# core.net
KiCad netlist of a schematic drawn in EAGLE
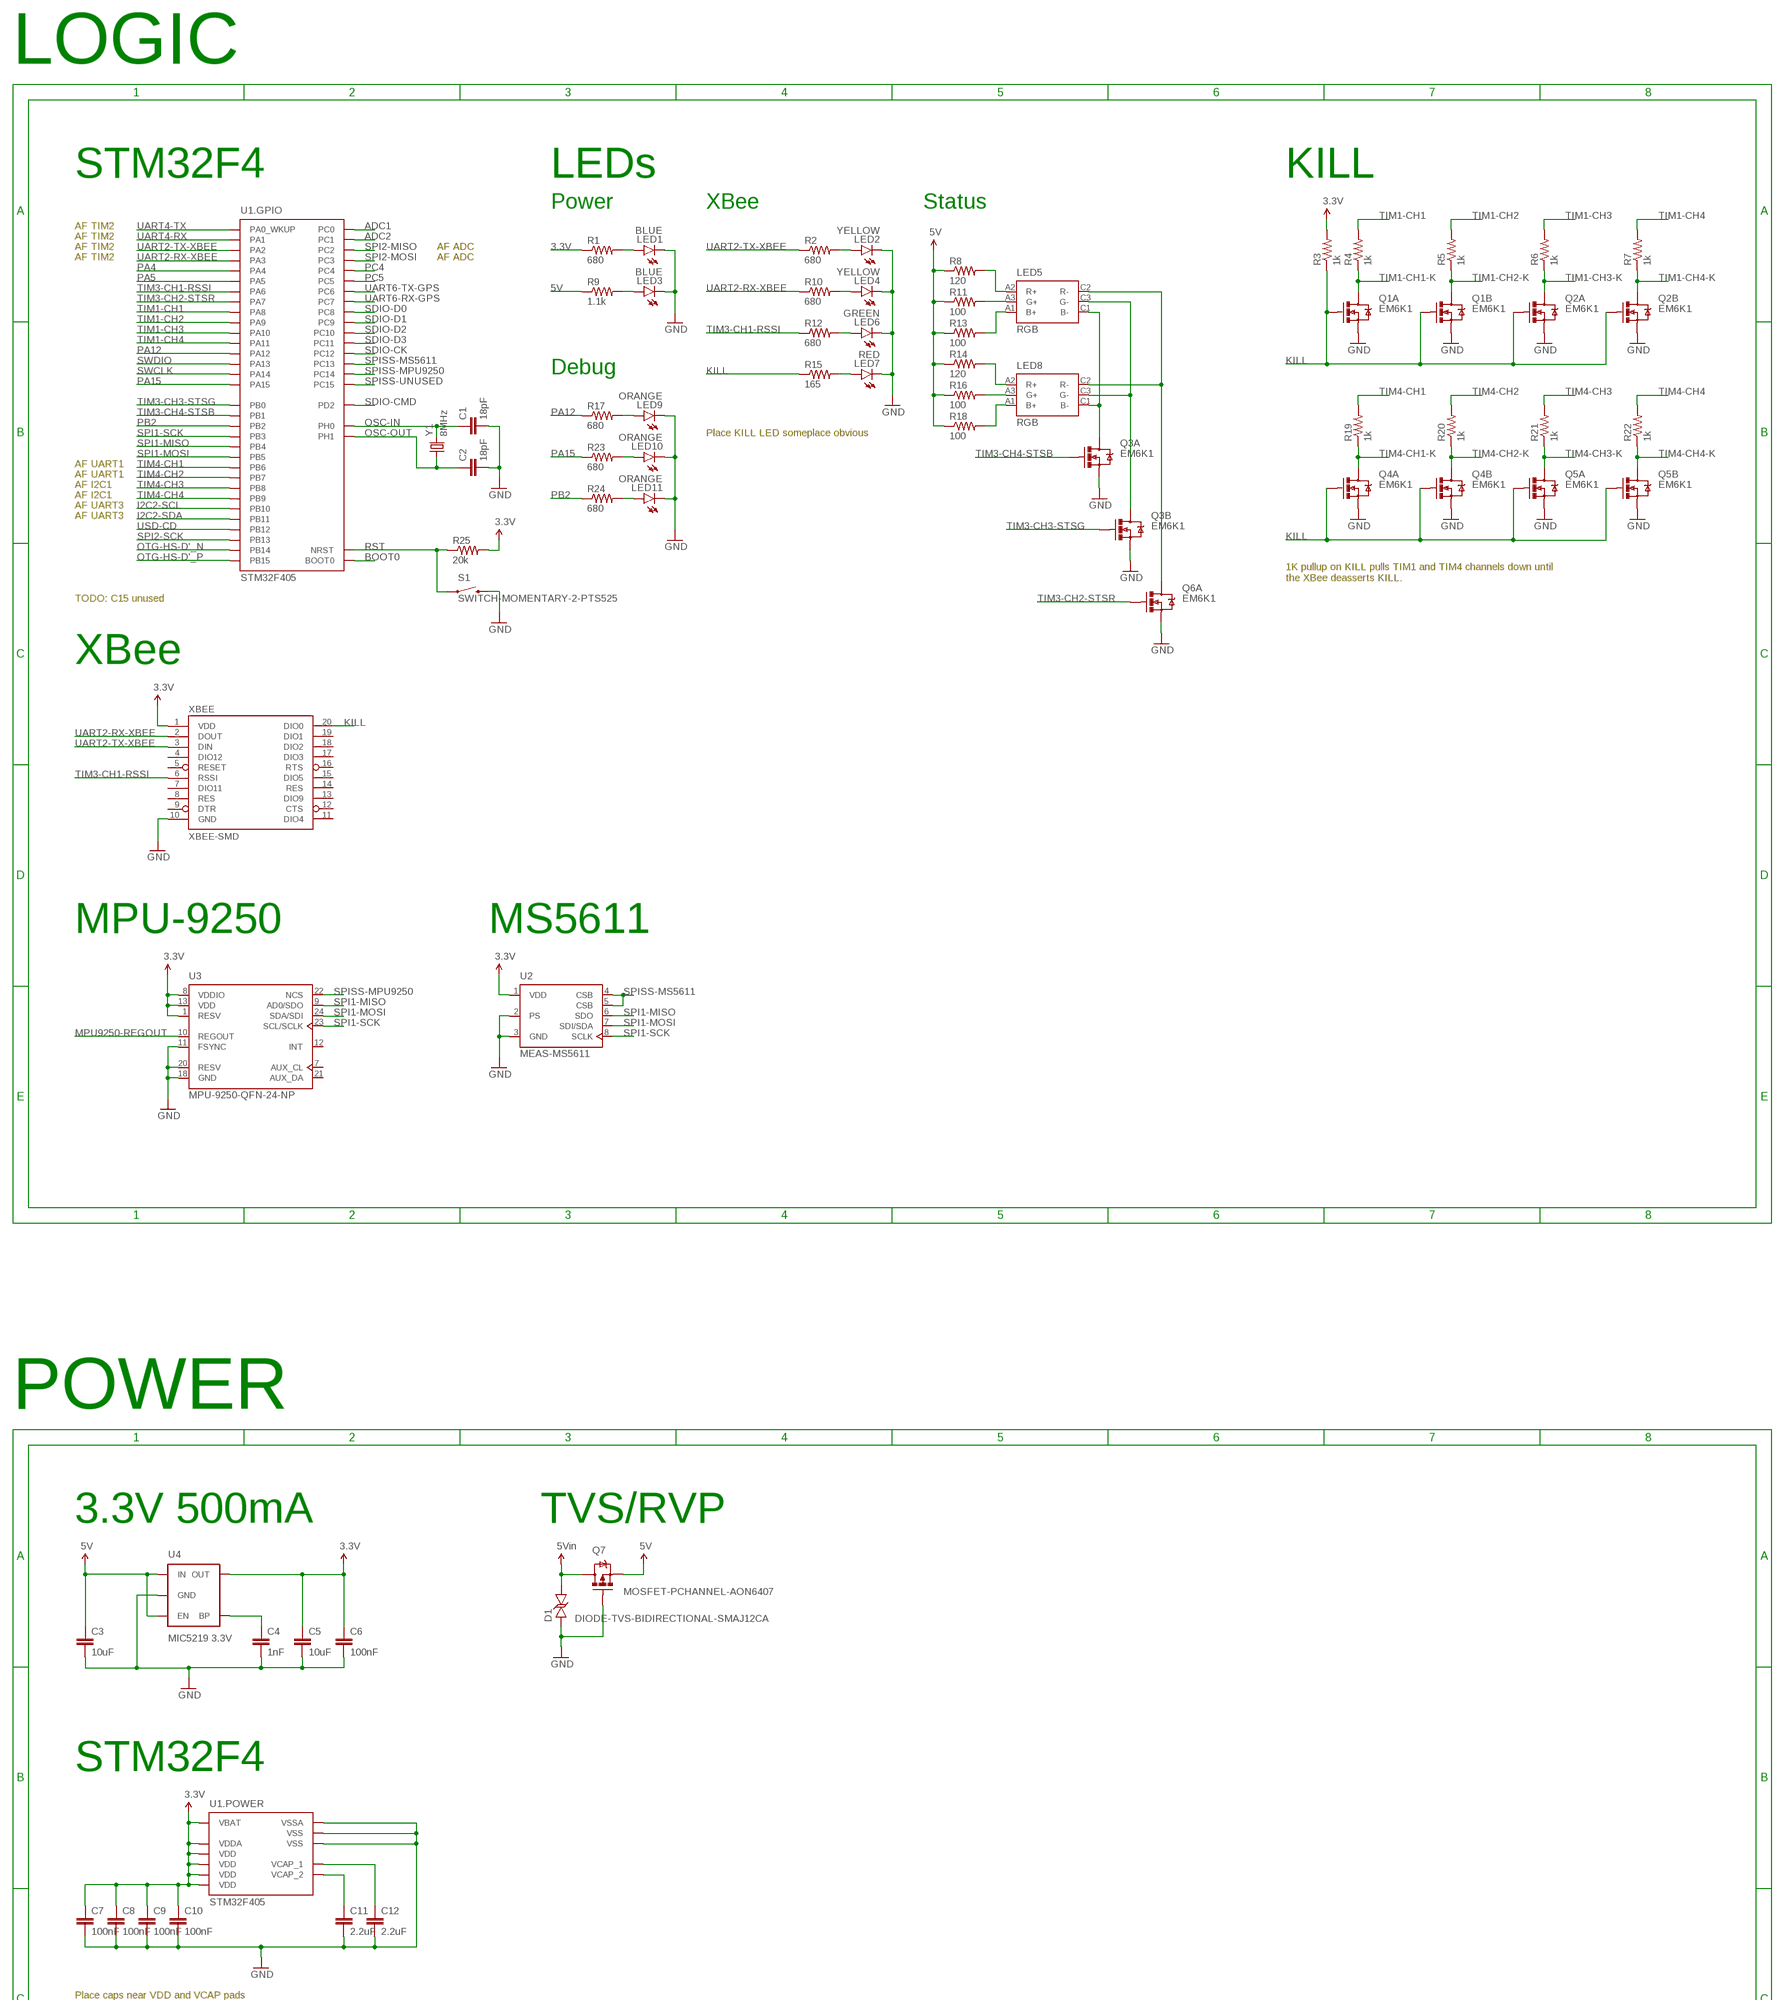
[diagram p0: schematic, sheet 1, part 1 of 2]
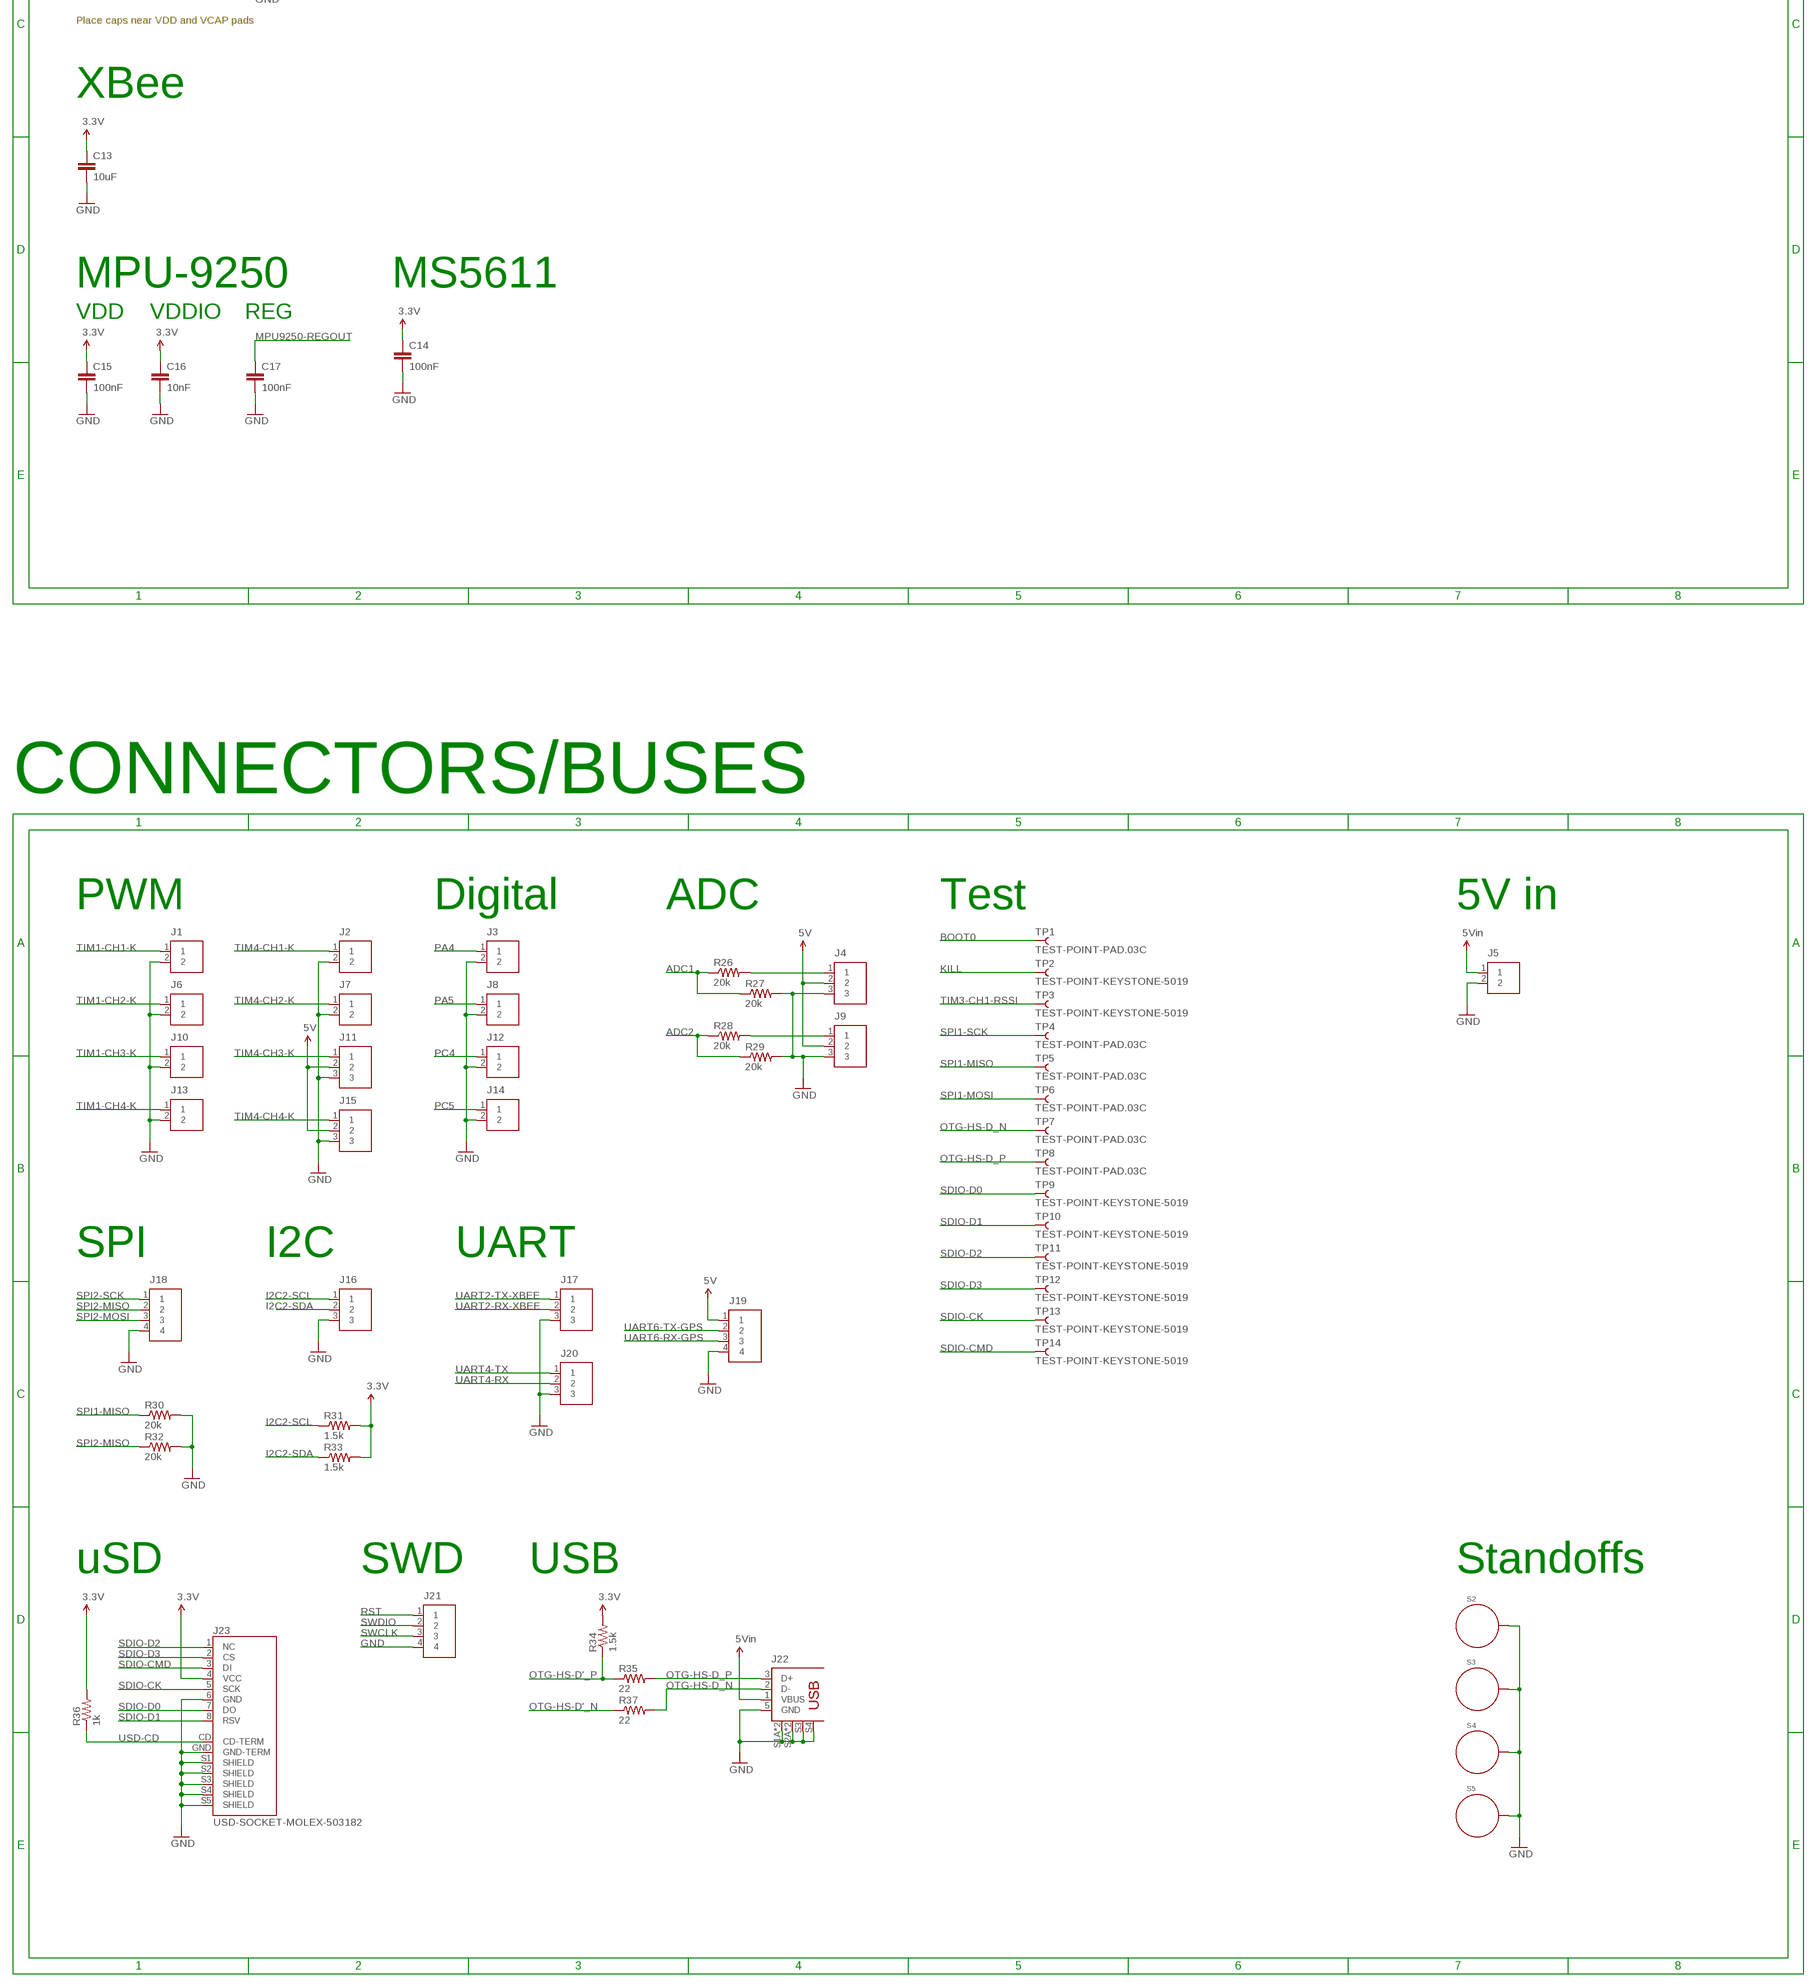
[diagram p1: schematic, sheet 1, part 2 of 2]

(export (version "E")
  (design (tool "Eeschema 10.0.6"))
  (components
    (comp (ref "C1")
      (value "18pF")
      (footprint "eagle-import:0603")
      (libsource (lib "eagle-import") (part "CAP-18PF-50V-5%(0603)"))
    )
    (comp (ref "C2")
      (value "18pF")
      (footprint "eagle-import:0603")
      (libsource (lib "eagle-import") (part "CAP-18PF-50V-5%(0603)"))
    )
    (comp (ref "C3")
      (value "10uF")
      (footprint "eagle-import:0805")
      (libsource (lib "eagle-import") (part "CAP-10UF-10V-10%(0805)"))
    )
    (comp (ref "C4")
      (value "1nF")
      (footprint "eagle-import:0603")
      (libsource (lib "eagle-import") (part "CAP-1NF-50V-10%(0603)"))
    )
    (comp (ref "C5")
      (value "10uF")
      (footprint "eagle-import:0805")
      (libsource (lib "eagle-import") (part "CAP-10UF-10V-10%(0805)"))
    )
    (comp (ref "C6")
      (value "100nF")
      (footprint "eagle-import:0603")
      (libsource (lib "eagle-import") (part "CAP-100NF-16V-10%(0603)"))
    )
    (comp (ref "C7")
      (value "100nF")
      (footprint "eagle-import:0603")
      (libsource (lib "eagle-import") (part "CAP-100NF-16V-10%(0603)"))
    )
    (comp (ref "C8")
      (value "100nF")
      (footprint "eagle-import:0603")
      (libsource (lib "eagle-import") (part "CAP-100NF-16V-10%(0603)"))
    )
    (comp (ref "C9")
      (value "100nF")
      (footprint "eagle-import:0603")
      (libsource (lib "eagle-import") (part "CAP-100NF-16V-10%(0603)"))
    )
    (comp (ref "C10")
      (value "100nF")
      (footprint "eagle-import:0603")
      (libsource (lib "eagle-import") (part "CAP-100NF-16V-10%(0603)"))
    )
    (comp (ref "C11")
      (value "2.2uF")
      (footprint "eagle-import:0603")
      (libsource (lib "eagle-import") (part "CAP-2.2UF-10V-10%(0603)"))
    )
    (comp (ref "C12")
      (value "2.2uF")
      (footprint "eagle-import:0603")
      (libsource (lib "eagle-import") (part "CAP-2.2UF-10V-10%(0603)"))
    )
    (comp (ref "C13")
      (value "10uF")
      (footprint "eagle-import:0805")
      (libsource (lib "eagle-import") (part "CAP-10UF-10V-10%(0805)"))
    )
    (comp (ref "C14")
      (value "100nF")
      (footprint "eagle-import:0603")
      (libsource (lib "eagle-import") (part "CAP-100NF-16V-10%(0603)"))
    )
    (comp (ref "C15")
      (value "100nF")
      (footprint "eagle-import:0603")
      (libsource (lib "eagle-import") (part "CAP-100NF-16V-10%(0603)"))
    )
    (comp (ref "C16")
      (value "10nF")
      (footprint "eagle-import:0603")
      (libsource (lib "eagle-import") (part "CAP-10NF-50V-10%(0603)"))
    )
    (comp (ref "C17")
      (value "100nF")
      (footprint "eagle-import:0603")
      (libsource (lib "eagle-import") (part "CAP-100NF-16V-10%(0603)"))
    )
    (comp (ref "D1")
      (value "DIODE-TVS-BIDIRECTIONAL-SMAJ12CA")
      (footprint "eagle-import:SMAJ")
      (libsource (lib "eagle-import") (part "DIODE-TVS-BIDIRECTIONAL-SMAJ12CA"))
    )
    (comp (ref "J1")
      (value "M02")
      (footprint "eagle-import:MOLEX-2MM-MICROLATCH-2POS-RA")
      (libsource (lib "eagle-import") (part "M02"))
    )
    (comp (ref "J2")
      (value "M02")
      (footprint "eagle-import:MOLEX-2MM-MICROLATCH-2POS-RA")
      (libsource (lib "eagle-import") (part "M02"))
    )
    (comp (ref "J3")
      (value "M02")
      (footprint "eagle-import:MOLEX-2MM-MICROLATCH-2POS-RA")
      (libsource (lib "eagle-import") (part "M02"))
    )
    (comp (ref "J4")
      (value "M03")
      (footprint "eagle-import:MOLEX-2MM-MICROLATCH-3POS-RA")
      (libsource (lib "eagle-import") (part "M03"))
    )
    (comp (ref "J5")
      (value "M02")
      (footprint "eagle-import:MOLEX-2MM-MICROLATCH-2POS-RA")
      (libsource (lib "eagle-import") (part "M02"))
    )
    (comp (ref "J6")
      (value "M02")
      (footprint "eagle-import:MOLEX-2MM-MICROLATCH-2POS-RA")
      (libsource (lib "eagle-import") (part "M02"))
    )
    (comp (ref "J7")
      (value "M02")
      (footprint "eagle-import:MOLEX-2MM-MICROLATCH-2POS-RA")
      (libsource (lib "eagle-import") (part "M02"))
    )
    (comp (ref "J8")
      (value "M02")
      (footprint "eagle-import:MOLEX-2MM-MICROLATCH-2POS-RA")
      (libsource (lib "eagle-import") (part "M02"))
    )
    (comp (ref "J9")
      (value "M03")
      (footprint "eagle-import:MOLEX-2MM-MICROLATCH-3POS-RA")
      (libsource (lib "eagle-import") (part "M03"))
    )
    (comp (ref "J10")
      (value "M02")
      (footprint "eagle-import:MOLEX-2MM-MICROLATCH-2POS-RA")
      (libsource (lib "eagle-import") (part "M02"))
    )
    (comp (ref "J11")
      (value "M03")
      (footprint "eagle-import:MOLEX-2MM-MICROLATCH-3POS-RA")
      (libsource (lib "eagle-import") (part "M03"))
    )
    (comp (ref "J12")
      (value "M02")
      (footprint "eagle-import:MOLEX-2MM-MICROLATCH-2POS-RA")
      (libsource (lib "eagle-import") (part "M02"))
    )
    (comp (ref "J13")
      (value "M02")
      (footprint "eagle-import:MOLEX-2MM-MICROLATCH-2POS-RA")
      (libsource (lib "eagle-import") (part "M02"))
    )
    (comp (ref "J14")
      (value "M02")
      (footprint "eagle-import:MOLEX-2MM-MICROLATCH-2POS-RA")
      (libsource (lib "eagle-import") (part "M02"))
    )
    (comp (ref "J15")
      (value "M03")
      (footprint "eagle-import:MOLEX-2MM-MICROLATCH-3POS-RA")
      (libsource (lib "eagle-import") (part "M03"))
    )
    (comp (ref "J16")
      (value "M03")
      (footprint "eagle-import:MOLEX-2MM-MICROLATCH-3POS-RA")
      (libsource (lib "eagle-import") (part "M03"))
    )
    (comp (ref "J17")
      (value "M03")
      (footprint "eagle-import:MOLEX-2MM-MICROLATCH-3POS-RA")
      (libsource (lib "eagle-import") (part "M03"))
    )
    (comp (ref "J18")
      (value "M04")
      (footprint "eagle-import:MOLEX-2MM-MICROLATCH-4POS-RA")
      (libsource (lib "eagle-import") (part "M04"))
    )
    (comp (ref "J19")
      (value "M04")
      (footprint "eagle-import:MOLEX-2MM-MICROLATCH-4POS-RA")
      (libsource (lib "eagle-import") (part "M04"))
    )
    (comp (ref "J20")
      (value "M03")
      (footprint "eagle-import:MOLEX-2MM-MICROLATCH-3POS-RA")
      (libsource (lib "eagle-import") (part "M03"))
    )
    (comp (ref "J21")
      (value "M04")
      (footprint "eagle-import:MOLEX-2MM-MICROLATCH-4POS-RA")
      (libsource (lib "eagle-import") (part "M04"))
    )
    (comp (ref "J22")
      (value "USB+SHIELD-MICROB-SMD-MOLEX")
      (footprint "eagle-import:USB-MICROB-SMD-MOLEX")
      (libsource (lib "eagle-import") (part "USB+SHIELD-MICROB-SMD-MOLEX"))
    )
    (comp (ref "J23")
      (value "USD-SOCKET-MOLEX-503182")
      (footprint "eagle-import:USD-SOCKET-PP-MOLEX-503182")
      (libsource (lib "eagle-import") (part "USD-SOCKET-MOLEX-503182"))
    )
    (comp (ref "LED1")
      (value "BLUE")
      (footprint "eagle-import:LED-0603")
      (libsource (lib "eagle-import") (part "LED-KINGBRIGHT-HELI-BLUE(0603)"))
    )
    (comp (ref "LED2")
      (value "YELLOW")
      (footprint "eagle-import:LED-0603")
      (libsource (lib "eagle-import") (part "LED-KINGBRIGHT-HELI-YELLOW(0603)"))
    )
    (comp (ref "LED3")
      (value "BLUE")
      (footprint "eagle-import:LED-0603")
      (libsource (lib "eagle-import") (part "LED-KINGBRIGHT-HELI-BLUE(0603)"))
    )
    (comp (ref "LED4")
      (value "YELLOW")
      (footprint "eagle-import:LED-0603")
      (libsource (lib "eagle-import") (part "LED-KINGBRIGHT-HELI-YELLOW(0603)"))
    )
    (comp (ref "LED5")
      (value "RGB")
      (footprint "eagle-import:PLCC-6")
      (libsource (lib "eagle-import") (part "OSRAM-MULTILED-RGB"))
    )
    (comp (ref "LED6")
      (value "GREEN")
      (footprint "eagle-import:LED-0603")
      (libsource (lib "eagle-import") (part "LED-KINGBRIGHT-HELI-GREEN(0603)"))
    )
    (comp (ref "LED7")
      (value "RED")
      (footprint "eagle-import:LED-0603")
      (libsource (lib "eagle-import") (part "LED-KINGBRIGHT-HELI-RED(0603)"))
    )
    (comp (ref "LED8")
      (value "RGB")
      (footprint "eagle-import:PLCC-6")
      (libsource (lib "eagle-import") (part "OSRAM-MULTILED-RGB"))
    )
    (comp (ref "LED9")
      (value "ORANGE")
      (footprint "eagle-import:LED-0603")
      (libsource (lib "eagle-import") (part "LED-KINGBRIGHT-HELI-ORANGE(0603)"))
    )
    (comp (ref "LED10")
      (value "ORANGE")
      (footprint "eagle-import:LED-0603")
      (libsource (lib "eagle-import") (part "LED-KINGBRIGHT-HELI-ORANGE(0603)"))
    )
    (comp (ref "LED11")
      (value "ORANGE")
      (footprint "eagle-import:LED-0603")
      (libsource (lib "eagle-import") (part "LED-KINGBRIGHT-HELI-ORANGE(0603)"))
    )
    (comp (ref "Q1")
      (value "EM6K1")
      (footprint "eagle-import:SOT-666")
      (libsource (lib "eagle-import") (part "MOSFET-NCHANNEL-DUAL-EM6K1"))
    )
    (comp (ref "Q2")
      (value "EM6K1")
      (footprint "eagle-import:SOT-666")
      (libsource (lib "eagle-import") (part "MOSFET-NCHANNEL-DUAL-EM6K1"))
    )
    (comp (ref "Q3")
      (value "EM6K1")
      (footprint "eagle-import:SOT-666")
      (libsource (lib "eagle-import") (part "MOSFET-NCHANNEL-DUAL-EM6K1"))
    )
    (comp (ref "Q4")
      (value "EM6K1")
      (footprint "eagle-import:SOT-666")
      (libsource (lib "eagle-import") (part "MOSFET-NCHANNEL-DUAL-EM6K1"))
    )
    (comp (ref "Q5")
      (value "EM6K1")
      (footprint "eagle-import:SOT-666")
      (libsource (lib "eagle-import") (part "MOSFET-NCHANNEL-DUAL-EM6K1"))
    )
    (comp (ref "Q6")
      (value "EM6K1")
      (footprint "eagle-import:SOT-666")
      (libsource (lib "eagle-import") (part "MOSFET-NCHANNEL-DUAL-EM6K1"))
    )
    (comp (ref "Q7")
      (value "MOSFET-PCHANNEL-AON6407")
      (footprint "eagle-import:DFN5X6")
      (libsource (lib "eagle-import") (part "MOSFET-PCHANNEL-AON6407"))
    )
    (comp (ref "R1")
      (value "680")
      (footprint "eagle-import:0603")
      (libsource (lib "eagle-import") (part "RES-680OHM-0.1W-5%(0603)"))
    )
    (comp (ref "R2")
      (value "680")
      (footprint "eagle-import:0603")
      (libsource (lib "eagle-import") (part "RES-680OHM-0.1W-5%(0603)"))
    )
    (comp (ref "R3")
      (value "1k")
      (footprint "eagle-import:0603")
      (libsource (lib "eagle-import") (part "RES-1KOHM-0.1W-5%(0603)"))
    )
    (comp (ref "R4")
      (value "1k")
      (footprint "eagle-import:0603")
      (libsource (lib "eagle-import") (part "RES-1KOHM-0.1W-5%(0603)"))
    )
    (comp (ref "R5")
      (value "1k")
      (footprint "eagle-import:0603")
      (libsource (lib "eagle-import") (part "RES-1KOHM-0.1W-5%(0603)"))
    )
    (comp (ref "R6")
      (value "1k")
      (footprint "eagle-import:0603")
      (libsource (lib "eagle-import") (part "RES-1KOHM-0.1W-5%(0603)"))
    )
    (comp (ref "R7")
      (value "1k")
      (footprint "eagle-import:0603")
      (libsource (lib "eagle-import") (part "RES-1KOHM-0.1W-5%(0603)"))
    )
    (comp (ref "R8")
      (value "120")
      (footprint "eagle-import:0603")
      (libsource (lib "eagle-import") (part "RES-120OHM-0.1W-5%(0603)"))
    )
    (comp (ref "R9")
      (value "1.1k")
      (footprint "eagle-import:0603")
      (libsource (lib "eagle-import") (part "RES-1.1KOHM-0.1W-5%(0603)"))
    )
    (comp (ref "R10")
      (value "680")
      (footprint "eagle-import:0603")
      (libsource (lib "eagle-import") (part "RES-680OHM-0.1W-5%(0603)"))
    )
    (comp (ref "R11")
      (value "100")
      (footprint "eagle-import:0603")
      (libsource (lib "eagle-import") (part "RES-100OHM-0.1W-5%(0603)"))
    )
    (comp (ref "R12")
      (value "680")
      (footprint "eagle-import:0603")
      (libsource (lib "eagle-import") (part "RES-680OHM-0.1W-5%(0603)"))
    )
    (comp (ref "R13")
      (value "100")
      (footprint "eagle-import:0603")
      (libsource (lib "eagle-import") (part "RES-100OHM-0.1W-5%(0603)"))
    )
    (comp (ref "R14")
      (value "120")
      (footprint "eagle-import:0603")
      (libsource (lib "eagle-import") (part "RES-120OHM-0.1W-5%(0603)"))
    )
    (comp (ref "R15")
      (value "165")
      (footprint "eagle-import:0603")
      (libsource (lib "eagle-import") (part "RES-165OHM-0.1W-1%(0603)"))
    )
    (comp (ref "R16")
      (value "100")
      (footprint "eagle-import:0603")
      (libsource (lib "eagle-import") (part "RES-100OHM-0.1W-5%(0603)"))
    )
    (comp (ref "R17")
      (value "680")
      (footprint "eagle-import:0603")
      (libsource (lib "eagle-import") (part "RES-680OHM-0.1W-5%(0603)"))
    )
    (comp (ref "R18")
      (value "100")
      (footprint "eagle-import:0603")
      (libsource (lib "eagle-import") (part "RES-100OHM-0.1W-5%(0603)"))
    )
    (comp (ref "R19")
      (value "1k")
      (footprint "eagle-import:0603")
      (libsource (lib "eagle-import") (part "RES-1KOHM-0.1W-5%(0603)"))
    )
    (comp (ref "R20")
      (value "1k")
      (footprint "eagle-import:0603")
      (libsource (lib "eagle-import") (part "RES-1KOHM-0.1W-5%(0603)"))
    )
    (comp (ref "R21")
      (value "1k")
      (footprint "eagle-import:0603")
      (libsource (lib "eagle-import") (part "RES-1KOHM-0.1W-5%(0603)"))
    )
    (comp (ref "R22")
      (value "1k")
      (footprint "eagle-import:0603")
      (libsource (lib "eagle-import") (part "RES-1KOHM-0.1W-5%(0603)"))
    )
    (comp (ref "R23")
      (value "680")
      (footprint "eagle-import:0603")
      (libsource (lib "eagle-import") (part "RES-680OHM-0.1W-5%(0603)"))
    )
    (comp (ref "R24")
      (value "680")
      (footprint "eagle-import:0603")
      (libsource (lib "eagle-import") (part "RES-680OHM-0.1W-5%(0603)"))
    )
    (comp (ref "R25")
      (value "20k")
      (footprint "eagle-import:0603")
      (libsource (lib "eagle-import") (part "RES-20KOHM-0.1W-1%(0603)"))
    )
    (comp (ref "R26")
      (value "20k")
      (footprint "eagle-import:0603")
      (libsource (lib "eagle-import") (part "RES-20KOHM-0.1W-0.1%(0603)"))
    )
    (comp (ref "R27")
      (value "20k")
      (footprint "eagle-import:0603")
      (libsource (lib "eagle-import") (part "RES-20KOHM-0.1W-0.1%(0603)"))
    )
    (comp (ref "R28")
      (value "20k")
      (footprint "eagle-import:0603")
      (libsource (lib "eagle-import") (part "RES-20KOHM-0.1W-0.1%(0603)"))
    )
    (comp (ref "R29")
      (value "20k")
      (footprint "eagle-import:0603")
      (libsource (lib "eagle-import") (part "RES-20KOHM-0.1W-0.1%(0603)"))
    )
    (comp (ref "R30")
      (value "20k")
      (footprint "eagle-import:0603")
      (libsource (lib "eagle-import") (part "RES-20KOHM-0.1W-1%(0603)"))
    )
    (comp (ref "R31")
      (value "1.5k")
      (footprint "eagle-import:0603")
      (libsource (lib "eagle-import") (part "RES-1.5KOHM-0.1W-5%(0603)"))
    )
    (comp (ref "R32")
      (value "20k")
      (footprint "eagle-import:0603")
      (libsource (lib "eagle-import") (part "RES-20KOHM-0.1W-1%(0603)"))
    )
    (comp (ref "R33")
      (value "1.5k")
      (footprint "eagle-import:0603")
      (libsource (lib "eagle-import") (part "RES-1.5KOHM-0.1W-5%(0603)"))
    )
    (comp (ref "R34")
      (value "1.5k")
      (footprint "eagle-import:0603")
      (libsource (lib "eagle-import") (part "RES-1.5KOHM-0.1W-5%(0603)"))
    )
    (comp (ref "R35")
      (value "22")
      (footprint "eagle-import:0603")
      (libsource (lib "eagle-import") (part "RES-22OHM-0.1W-5%(0603)"))
    )
    (comp (ref "R36")
      (value "1k")
      (footprint "eagle-import:0603")
      (libsource (lib "eagle-import") (part "RES-1KOHM-0.1W-5%(0603)"))
    )
    (comp (ref "R37")
      (value "22")
      (footprint "eagle-import:0603")
      (libsource (lib "eagle-import") (part "RES-22OHM-0.1W-5%(0603)"))
    )
    (comp (ref "S1")
      (value "SWITCH-MOMENTARY-2-PTS525")
      (footprint "eagle-import:TACTILE-SWITCH-SMD")
      (libsource (lib "eagle-import") (part "SWITCH-MOMENTARY-2-PTS525"))
    )
    (comp (ref "S2")
      (value "STANDOFF_ELECTRICAL-#4")
      (footprint "eagle-import:STANDOFF-ELECTRICAL-#4")
      (libsource (lib "eagle-import") (part "STANDOFF_ELECTRICAL-#4"))
    )
    (comp (ref "S3")
      (value "STANDOFF_ELECTRICAL-#4")
      (footprint "eagle-import:STANDOFF-ELECTRICAL-#4")
      (libsource (lib "eagle-import") (part "STANDOFF_ELECTRICAL-#4"))
    )
    (comp (ref "S4")
      (value "STANDOFF_ELECTRICAL-#4")
      (footprint "eagle-import:STANDOFF-ELECTRICAL-#4")
      (libsource (lib "eagle-import") (part "STANDOFF_ELECTRICAL-#4"))
    )
    (comp (ref "S5")
      (value "STANDOFF_ELECTRICAL-#4")
      (footprint "eagle-import:STANDOFF-ELECTRICAL-#4")
      (libsource (lib "eagle-import") (part "STANDOFF_ELECTRICAL-#4"))
    )
    (comp (ref "TP1")
      (value "TEST-POINT-PAD.03C")
      (footprint "eagle-import:PAD-.03C")
      (libsource (lib "eagle-import") (part "TEST-POINT-PAD.03C"))
    )
    (comp (ref "TP2")
      (value "TEST-POINT-KEYSTONE-5019")
      (footprint "eagle-import:PAD.15X.08")
      (libsource (lib "eagle-import") (part "TEST-POINT-KEYSTONE-5019"))
    )
    (comp (ref "TP3")
      (value "TEST-POINT-KEYSTONE-5019")
      (footprint "eagle-import:PAD.15X.08")
      (libsource (lib "eagle-import") (part "TEST-POINT-KEYSTONE-5019"))
    )
    (comp (ref "TP4")
      (value "TEST-POINT-PAD.03C")
      (footprint "eagle-import:PAD-.03C")
      (libsource (lib "eagle-import") (part "TEST-POINT-PAD.03C"))
    )
    (comp (ref "TP5")
      (value "TEST-POINT-PAD.03C")
      (footprint "eagle-import:PAD-.03C")
      (libsource (lib "eagle-import") (part "TEST-POINT-PAD.03C"))
    )
    (comp (ref "TP6")
      (value "TEST-POINT-PAD.03C")
      (footprint "eagle-import:PAD-.03C")
      (libsource (lib "eagle-import") (part "TEST-POINT-PAD.03C"))
    )
    (comp (ref "TP7")
      (value "TEST-POINT-PAD.03C")
      (footprint "eagle-import:PAD-.03C")
      (libsource (lib "eagle-import") (part "TEST-POINT-PAD.03C"))
    )
    (comp (ref "TP8")
      (value "TEST-POINT-PAD.03C")
      (footprint "eagle-import:PAD-.03C")
      (libsource (lib "eagle-import") (part "TEST-POINT-PAD.03C"))
    )
    (comp (ref "TP9")
      (value "TEST-POINT-KEYSTONE-5019")
      (footprint "eagle-import:PAD.15X.08")
      (libsource (lib "eagle-import") (part "TEST-POINT-KEYSTONE-5019"))
    )
    (comp (ref "TP10")
      (value "TEST-POINT-KEYSTONE-5019")
      (footprint "eagle-import:PAD.15X.08")
      (libsource (lib "eagle-import") (part "TEST-POINT-KEYSTONE-5019"))
    )
    (comp (ref "TP11")
      (value "TEST-POINT-KEYSTONE-5019")
      (footprint "eagle-import:PAD.15X.08")
      (libsource (lib "eagle-import") (part "TEST-POINT-KEYSTONE-5019"))
    )
    (comp (ref "TP12")
      (value "TEST-POINT-KEYSTONE-5019")
      (footprint "eagle-import:PAD.15X.08")
      (libsource (lib "eagle-import") (part "TEST-POINT-KEYSTONE-5019"))
    )
    (comp (ref "TP13")
      (value "TEST-POINT-KEYSTONE-5019")
      (footprint "eagle-import:PAD.15X.08")
      (libsource (lib "eagle-import") (part "TEST-POINT-KEYSTONE-5019"))
    )
    (comp (ref "TP14")
      (value "TEST-POINT-KEYSTONE-5019")
      (footprint "eagle-import:PAD.15X.08")
      (libsource (lib "eagle-import") (part "TEST-POINT-KEYSTONE-5019"))
    )
    (comp (ref "U1")
      (value "STM32F405")
      (footprint "eagle-import:LQFP-64-STM32F405")
      (libsource (lib "eagle-import") (part "STM32F405"))
    )
    (comp (ref "U2")
      (value "MEAS-MS5611")
      (footprint "eagle-import:MEAS-MS5611")
      (libsource (lib "eagle-import") (part "MEAS-MS5611"))
    )
    (comp (ref "U3")
      (value "MPU-9250-QFN-24-NP")
      (footprint "eagle-import:QFN-24-NP")
      (libsource (lib "eagle-import") (part "MPU-9250-QFN-24-NP"))
    )
    (comp (ref "U4")
      (value "MIC5219 3.3V")
      (footprint "eagle-import:SOT23-5")
      (libsource (lib "eagle-import") (part "V-REG-MIC5219-3.3V"))
    )
    (comp (ref "XBEE")
      (value "XBEE-SMD")
      (footprint "eagle-import:XBEE-SMD")
      (libsource (lib "eagle-import") (part "XBEE-SMD"))
    )
    (comp (ref "Y1")
      (value "8MHz")
      (footprint "eagle-import:CX532")
      (libsource (lib "eagle-import") (part "CRYSTAL-8MHZ-CX532"))
    )
  )
  (nets
    (net (code "1") (name "/ADC1") (class "Default")
      (node (ref "R26") (pin "1") (pinfunction "1_1") (pintype "passive"))
      (node (ref "R27") (pin "1") (pinfunction "1_1") (pintype "passive"))
      (node (ref "U1") (pin "8") (pinfunction "PC0_8") (pintype "bidirectional"))
    )
    (net (code "2") (name "/ADC2") (class "Default")
      (node (ref "R28") (pin "1") (pinfunction "1_1") (pintype "passive"))
      (node (ref "R29") (pin "1") (pinfunction "1_1") (pintype "passive"))
      (node (ref "U1") (pin "9") (pinfunction "PC1_9") (pintype "bidirectional"))
    )
    (net (code "3") (name "/BOOT0") (class "Default")
      (node (ref "TP1") (pin "1") (pinfunction "1_1") (pintype "bidirectional"))
      (node (ref "U1") (pin "60") (pinfunction "BOOT0_60") (pintype "bidirectional"))
    )
    (net (code "4") (name "/I2C2-SCL") (class "Default")
      (node (ref "J16") (pin "1") (pinfunction "1_1") (pintype "bidirectional"))
      (node (ref "R31") (pin "1") (pinfunction "1_1") (pintype "passive"))
      (node (ref "U1") (pin "29") (pinfunction "PB10_29") (pintype "bidirectional"))
    )
    (net (code "5") (name "/I2C2-SDA") (class "Default")
      (node (ref "J16") (pin "2") (pinfunction "2_2") (pintype "bidirectional"))
      (node (ref "R33") (pin "1") (pinfunction "1_1") (pintype "passive"))
      (node (ref "U1") (pin "30") (pinfunction "PB11_30") (pintype "bidirectional"))
    )
    (net (code "6") (name "/KILL") (class "Default")
      (node (ref "Q1") (pin "2") (pinfunction "G_2") (pintype "passive"))
      (node (ref "Q1") (pin "5") (pinfunction "G_5") (pintype "passive"))
      (node (ref "Q2") (pin "2") (pinfunction "G_2") (pintype "passive"))
      (node (ref "Q2") (pin "5") (pinfunction "G_5") (pintype "passive"))
      (node (ref "Q4") (pin "2") (pinfunction "G_2") (pintype "passive"))
      (node (ref "Q4") (pin "5") (pinfunction "G_5") (pintype "passive"))
      (node (ref "Q5") (pin "2") (pinfunction "G_2") (pintype "passive"))
      (node (ref "Q5") (pin "5") (pinfunction "G_5") (pintype "passive"))
      (node (ref "R15") (pin "1") (pinfunction "1_1") (pintype "passive"))
      (node (ref "R3") (pin "1") (pinfunction "1_1") (pintype "passive"))
      (node (ref "TP2") (pin "1") (pinfunction "1_1") (pintype "bidirectional"))
      (node (ref "XBEE") (pin "20") (pinfunction "DIO0_20") (pintype "bidirectional"))
    )
    (net (code "7") (name "/MPU9250-REGOUT") (class "Default")
      (node (ref "C17") (pin "2") (pinfunction "2_2") (pintype "passive"))
      (node (ref "U3") (pin "10") (pinfunction "REGOUT_10") (pintype "bidirectional"))
    )
    (net (code "8") (name "/OSC-IN") (class "Default")
      (node (ref "C1") (pin "2") (pinfunction "2_2") (pintype "passive"))
      (node (ref "U1") (pin "5") (pinfunction "PH0_5") (pintype "bidirectional"))
      (node (ref "Y1") (pin "2") (pinfunction "2_2") (pintype "passive"))
    )
    (net (code "9") (name "/OSC-OUT") (class "Default")
      (node (ref "C2") (pin "2") (pinfunction "2_2") (pintype "passive"))
      (node (ref "U1") (pin "6") (pinfunction "PH1_6") (pintype "bidirectional"))
      (node (ref "Y1") (pin "1") (pinfunction "1_1") (pintype "passive"))
    )
    (net (code "10") (name "/OTG-HS-D'_N") (class "Default")
      (node (ref "R37") (pin "1") (pinfunction "1_1") (pintype "passive"))
      (node (ref "U1") (pin "35") (pinfunction "PB14_35") (pintype "bidirectional"))
    )
    (net (code "11") (name "/OTG-HS-D'_P") (class "Default")
      (node (ref "R34") (pin "1") (pinfunction "1_1") (pintype "passive"))
      (node (ref "R35") (pin "1") (pinfunction "1_1") (pintype "passive"))
      (node (ref "U1") (pin "36") (pinfunction "PB15_36") (pintype "bidirectional"))
    )
    (net (code "12") (name "/OTG-HS-D_N") (class "Default")
      (node (ref "J22") (pin "2") (pinfunction "D-_2") (pintype "bidirectional"))
      (node (ref "R37") (pin "2") (pinfunction "2_2") (pintype "passive"))
      (node (ref "TP7") (pin "1") (pinfunction "1_1") (pintype "bidirectional"))
    )
    (net (code "13") (name "/OTG-HS-D_P") (class "Default")
      (node (ref "J22") (pin "3") (pinfunction "D+_3") (pintype "bidirectional"))
      (node (ref "R35") (pin "2") (pinfunction "2_2") (pintype "passive"))
      (node (ref "TP8") (pin "1") (pinfunction "1_1") (pintype "bidirectional"))
    )
    (net (code "14") (name "/PA4") (class "Default")
      (node (ref "J3") (pin "1") (pinfunction "1_1") (pintype "bidirectional"))
      (node (ref "U1") (pin "20") (pinfunction "PA4_20") (pintype "bidirectional"))
    )
    (net (code "15") (name "/PA5") (class "Default")
      (node (ref "J8") (pin "1") (pinfunction "1_1") (pintype "bidirectional"))
      (node (ref "U1") (pin "21") (pinfunction "PA5_21") (pintype "bidirectional"))
    )
    (net (code "16") (name "/PA12") (class "Default")
      (node (ref "R17") (pin "1") (pinfunction "1_1") (pintype "passive"))
      (node (ref "U1") (pin "45") (pinfunction "PA12_45") (pintype "bidirectional"))
    )
    (net (code "17") (name "/PA15") (class "Default")
      (node (ref "R23") (pin "1") (pinfunction "1_1") (pintype "passive"))
      (node (ref "U1") (pin "50") (pinfunction "PA15_50") (pintype "bidirectional"))
    )
    (net (code "18") (name "/PB2") (class "Default")
      (node (ref "R24") (pin "1") (pinfunction "1_1") (pintype "passive"))
      (node (ref "U1") (pin "28") (pinfunction "PB2_28") (pintype "bidirectional"))
    )
    (net (code "19") (name "/PC4") (class "Default")
      (node (ref "J12") (pin "1") (pinfunction "1_1") (pintype "bidirectional"))
      (node (ref "U1") (pin "24") (pinfunction "PC4_24") (pintype "bidirectional"))
    )
    (net (code "20") (name "/PC5") (class "Default")
      (node (ref "J14") (pin "1") (pinfunction "1_1") (pintype "bidirectional"))
      (node (ref "U1") (pin "25") (pinfunction "PC5_25") (pintype "bidirectional"))
    )
    (net (code "21") (name "/RST") (class "Default")
      (node (ref "J21") (pin "1") (pinfunction "1_1") (pintype "bidirectional"))
      (node (ref "R25") (pin "1") (pinfunction "1_1") (pintype "passive"))
      (node (ref "S1") (pin "1") (pinfunction "1_1") (pintype "passive"))
      (node (ref "S1") (pin "2") (pinfunction "1_2") (pintype "passive"))
      (node (ref "U1") (pin "7") (pinfunction "NRST_7") (pintype "bidirectional"))
    )
    (net (code "22") (name "/SDIO-CK") (class "Default")
      (node (ref "J23") (pin "5") (pinfunction "SCK_5") (pintype "bidirectional"))
      (node (ref "TP13") (pin "1") (pinfunction "1_1") (pintype "bidirectional"))
      (node (ref "U1") (pin "53") (pinfunction "PC12_53") (pintype "bidirectional"))
    )
    (net (code "23") (name "/SDIO-CMD") (class "Default")
      (node (ref "J23") (pin "3") (pinfunction "DI_3") (pintype "bidirectional"))
      (node (ref "TP14") (pin "1") (pinfunction "1_1") (pintype "bidirectional"))
      (node (ref "U1") (pin "54") (pinfunction "PD2_54") (pintype "bidirectional"))
    )
    (net (code "24") (name "/SDIO-D0") (class "Default")
      (node (ref "J23") (pin "7") (pinfunction "DO_7") (pintype "bidirectional"))
      (node (ref "TP9") (pin "1") (pinfunction "1_1") (pintype "bidirectional"))
      (node (ref "U1") (pin "39") (pinfunction "PC8_39") (pintype "bidirectional"))
    )
    (net (code "25") (name "/SDIO-D1") (class "Default")
      (node (ref "J23") (pin "8") (pinfunction "RSV_8") (pintype "bidirectional"))
      (node (ref "TP10") (pin "1") (pinfunction "1_1") (pintype "bidirectional"))
      (node (ref "U1") (pin "40") (pinfunction "PC9_40") (pintype "bidirectional"))
    )
    (net (code "26") (name "/SDIO-D2") (class "Default")
      (node (ref "J23") (pin "1") (pinfunction "NC_1") (pintype "bidirectional"))
      (node (ref "TP11") (pin "1") (pinfunction "1_1") (pintype "bidirectional"))
      (node (ref "U1") (pin "51") (pinfunction "PC10_51") (pintype "bidirectional"))
    )
    (net (code "27") (name "/SDIO-D3") (class "Default")
      (node (ref "J23") (pin "2") (pinfunction "CS_2") (pintype "bidirectional"))
      (node (ref "TP12") (pin "1") (pinfunction "1_1") (pintype "bidirectional"))
      (node (ref "U1") (pin "52") (pinfunction "PC11_52") (pintype "bidirectional"))
    )
    (net (code "28") (name "/SPI1-MISO") (class "Default")
      (node (ref "R30") (pin "1") (pinfunction "1_1") (pintype "passive"))
      (node (ref "TP5") (pin "1") (pinfunction "1_1") (pintype "bidirectional"))
      (node (ref "U1") (pin "56") (pinfunction "PB4_56") (pintype "bidirectional"))
      (node (ref "U2") (pin "6") (pinfunction "SDO_6") (pintype "output"))
      (node (ref "U3") (pin "9") (pinfunction "AD0/SDO_9") (pintype "bidirectional"))
    )
    (net (code "29") (name "/SPI1-MOSI") (class "Default")
      (node (ref "TP6") (pin "1") (pinfunction "1_1") (pintype "bidirectional"))
      (node (ref "U1") (pin "57") (pinfunction "PB5_57") (pintype "bidirectional"))
      (node (ref "U2") (pin "7") (pinfunction "SDI/SDA_7") (pintype "bidirectional"))
      (node (ref "U3") (pin "24") (pinfunction "SDA/SDI_24") (pintype "bidirectional"))
    )
    (net (code "30") (name "/SPI1-SCK") (class "Default")
      (node (ref "TP4") (pin "1") (pinfunction "1_1") (pintype "bidirectional"))
      (node (ref "U1") (pin "55") (pinfunction "PB3_55") (pintype "bidirectional"))
      (node (ref "U2") (pin "8") (pinfunction "SCLK_8") (pintype "input"))
      (node (ref "U3") (pin "23") (pinfunction "SCL/SCLK_23") (pintype "bidirectional"))
    )
    (net (code "31") (name "/SPI2-MISO") (class "Default")
      (node (ref "J18") (pin "2") (pinfunction "2_2") (pintype "bidirectional"))
      (node (ref "R32") (pin "1") (pinfunction "1_1") (pintype "passive"))
      (node (ref "U1") (pin "10") (pinfunction "PC2_10") (pintype "bidirectional"))
    )
    (net (code "32") (name "/SPI2-MOSI") (class "Default")
      (node (ref "J18") (pin "3") (pinfunction "3_3") (pintype "bidirectional"))
      (node (ref "U1") (pin "11") (pinfunction "PC3_11") (pintype "bidirectional"))
    )
    (net (code "33") (name "/SPI2-SCK") (class "Default")
      (node (ref "J18") (pin "1") (pinfunction "1_1") (pintype "bidirectional"))
      (node (ref "U1") (pin "34") (pinfunction "PB13_34") (pintype "bidirectional"))
    )
    (net (code "34") (name "/SPISS-MPU9250") (class "Default")
      (node (ref "U1") (pin "3") (pinfunction "PC14_3") (pintype "bidirectional"))
      (node (ref "U3") (pin "22") (pinfunction "NCS_22") (pintype "bidirectional"))
    )
    (net (code "35") (name "/SPISS-MS5611") (class "Default")
      (node (ref "U1") (pin "2") (pinfunction "PC13_2") (pintype "bidirectional"))
      (node (ref "U2") (pin "4") (pinfunction "CSB_4") (pintype "input"))
      (node (ref "U2") (pin "5") (pinfunction "CSB_5") (pintype "input"))
    )
    (net (code "36") (name "/SPISS-UNUSED") (class "Default")
      (node (ref "U1") (pin "4") (pinfunction "PC15_4") (pintype "bidirectional"))
    )
    (net (code "37") (name "/SWCLK") (class "Default")
      (node (ref "J21") (pin "3") (pinfunction "3_3") (pintype "bidirectional"))
      (node (ref "U1") (pin "49") (pinfunction "PA14_49") (pintype "bidirectional"))
    )
    (net (code "38") (name "/SWDIO") (class "Default")
      (node (ref "J21") (pin "2") (pinfunction "2_2") (pintype "bidirectional"))
      (node (ref "U1") (pin "46") (pinfunction "PA13_46") (pintype "bidirectional"))
    )
    (net (code "39") (name "/TIM1-CH1") (class "Default")
      (node (ref "R4") (pin "2") (pinfunction "2_2") (pintype "passive"))
      (node (ref "U1") (pin "41") (pinfunction "PA8_41") (pintype "bidirectional"))
    )
    (net (code "40") (name "/TIM1-CH1-K") (class "Default")
      (node (ref "J1") (pin "1") (pinfunction "1_1") (pintype "bidirectional"))
      (node (ref "Q1") (pin "6") (pinfunction "D_6") (pintype "passive"))
      (node (ref "R4") (pin "1") (pinfunction "1_1") (pintype "passive"))
    )
    (net (code "41") (name "/TIM1-CH2") (class "Default")
      (node (ref "R5") (pin "2") (pinfunction "2_2") (pintype "passive"))
      (node (ref "U1") (pin "42") (pinfunction "PA9_42") (pintype "bidirectional"))
    )
    (net (code "42") (name "/TIM1-CH2-K") (class "Default")
      (node (ref "J6") (pin "1") (pinfunction "1_1") (pintype "bidirectional"))
      (node (ref "Q1") (pin "3") (pinfunction "D_3") (pintype "passive"))
      (node (ref "R5") (pin "1") (pinfunction "1_1") (pintype "passive"))
    )
    (net (code "43") (name "/TIM1-CH3") (class "Default")
      (node (ref "R6") (pin "2") (pinfunction "2_2") (pintype "passive"))
      (node (ref "U1") (pin "43") (pinfunction "PA10_43") (pintype "bidirectional"))
    )
    (net (code "44") (name "/TIM1-CH3-K") (class "Default")
      (node (ref "J10") (pin "1") (pinfunction "1_1") (pintype "bidirectional"))
      (node (ref "Q2") (pin "6") (pinfunction "D_6") (pintype "passive"))
      (node (ref "R6") (pin "1") (pinfunction "1_1") (pintype "passive"))
    )
    (net (code "45") (name "/TIM1-CH4") (class "Default")
      (node (ref "R7") (pin "2") (pinfunction "2_2") (pintype "passive"))
      (node (ref "U1") (pin "44") (pinfunction "PA11_44") (pintype "bidirectional"))
    )
    (net (code "46") (name "/TIM1-CH4-K") (class "Default")
      (node (ref "J13") (pin "1") (pinfunction "1_1") (pintype "bidirectional"))
      (node (ref "Q2") (pin "3") (pinfunction "D_3") (pintype "passive"))
      (node (ref "R7") (pin "1") (pinfunction "1_1") (pintype "passive"))
    )
    (net (code "47") (name "/TIM3-CH1-RSSI") (class "Default")
      (node (ref "R12") (pin "1") (pinfunction "1_1") (pintype "passive"))
      (node (ref "TP3") (pin "1") (pinfunction "1_1") (pintype "bidirectional"))
      (node (ref "U1") (pin "22") (pinfunction "PA6_22") (pintype "bidirectional"))
      (node (ref "XBEE") (pin "6") (pinfunction "RSSI_6") (pintype "bidirectional"))
    )
    (net (code "48") (name "/TIM3-CH2-STSR") (class "Default")
      (node (ref "Q6") (pin "2") (pinfunction "G_2") (pintype "passive"))
      (node (ref "U1") (pin "23") (pinfunction "PA7_23") (pintype "bidirectional"))
    )
    (net (code "49") (name "/TIM3-CH3-STSG") (class "Default")
      (node (ref "Q3") (pin "5") (pinfunction "G_5") (pintype "passive"))
      (node (ref "U1") (pin "26") (pinfunction "PB0_26") (pintype "bidirectional"))
    )
    (net (code "50") (name "/TIM3-CH4-STSB") (class "Default")
      (node (ref "Q3") (pin "2") (pinfunction "G_2") (pintype "passive"))
      (node (ref "U1") (pin "27") (pinfunction "PB1_27") (pintype "bidirectional"))
    )
    (net (code "51") (name "/TIM4-CH1") (class "Default")
      (node (ref "R19") (pin "2") (pinfunction "2_2") (pintype "passive"))
      (node (ref "U1") (pin "58") (pinfunction "PB6_58") (pintype "bidirectional"))
    )
    (net (code "52") (name "/TIM4-CH1-K") (class "Default")
      (node (ref "J2") (pin "1") (pinfunction "1_1") (pintype "bidirectional"))
      (node (ref "Q4") (pin "6") (pinfunction "D_6") (pintype "passive"))
      (node (ref "R19") (pin "1") (pinfunction "1_1") (pintype "passive"))
    )
    (net (code "53") (name "/TIM4-CH2") (class "Default")
      (node (ref "R20") (pin "2") (pinfunction "2_2") (pintype "passive"))
      (node (ref "U1") (pin "59") (pinfunction "PB7_59") (pintype "bidirectional"))
    )
    (net (code "54") (name "/TIM4-CH2-K") (class "Default")
      (node (ref "J7") (pin "1") (pinfunction "1_1") (pintype "bidirectional"))
      (node (ref "Q4") (pin "3") (pinfunction "D_3") (pintype "passive"))
      (node (ref "R20") (pin "1") (pinfunction "1_1") (pintype "passive"))
    )
    (net (code "55") (name "/TIM4-CH3") (class "Default")
      (node (ref "R21") (pin "2") (pinfunction "2_2") (pintype "passive"))
      (node (ref "U1") (pin "61") (pinfunction "PB8_61") (pintype "bidirectional"))
    )
    (net (code "56") (name "/TIM4-CH3-K") (class "Default")
      (node (ref "J11") (pin "1") (pinfunction "1_1") (pintype "bidirectional"))
      (node (ref "Q5") (pin "6") (pinfunction "D_6") (pintype "passive"))
      (node (ref "R21") (pin "1") (pinfunction "1_1") (pintype "passive"))
    )
    (net (code "57") (name "/TIM4-CH4") (class "Default")
      (node (ref "R22") (pin "2") (pinfunction "2_2") (pintype "passive"))
      (node (ref "U1") (pin "62") (pinfunction "PB9_62") (pintype "bidirectional"))
    )
    (net (code "58") (name "/TIM4-CH4-K") (class "Default")
      (node (ref "J15") (pin "1") (pinfunction "1_1") (pintype "bidirectional"))
      (node (ref "Q5") (pin "3") (pinfunction "D_3") (pintype "passive"))
      (node (ref "R22") (pin "1") (pinfunction "1_1") (pintype "passive"))
    )
    (net (code "59") (name "/UART2-RX-XBEE") (class "Default")
      (node (ref "J17") (pin "2") (pinfunction "2_2") (pintype "bidirectional"))
      (node (ref "R10") (pin "1") (pinfunction "1_1") (pintype "passive"))
      (node (ref "U1") (pin "17") (pinfunction "PA3_17") (pintype "bidirectional"))
      (node (ref "XBEE") (pin "2") (pinfunction "DOUT_2") (pintype "output"))
    )
    (net (code "60") (name "/UART2-TX-XBEE") (class "Default")
      (node (ref "J17") (pin "1") (pinfunction "1_1") (pintype "bidirectional"))
      (node (ref "R2") (pin "1") (pinfunction "1_1") (pintype "passive"))
      (node (ref "U1") (pin "16") (pinfunction "PA2_16") (pintype "bidirectional"))
      (node (ref "XBEE") (pin "3") (pinfunction "DIN_3") (pintype "input"))
    )
    (net (code "61") (name "/UART4-RX") (class "Default")
      (node (ref "J20") (pin "2") (pinfunction "2_2") (pintype "bidirectional"))
      (node (ref "U1") (pin "15") (pinfunction "PA1_15") (pintype "bidirectional"))
    )
    (net (code "62") (name "/UART4-TX") (class "Default")
      (node (ref "J20") (pin "1") (pinfunction "1_1") (pintype "bidirectional"))
      (node (ref "U1") (pin "14") (pinfunction "PA0_WKUP_14") (pintype "bidirectional"))
    )
    (net (code "63") (name "/UART6-RX-GPS") (class "Default")
      (node (ref "J19") (pin "3") (pinfunction "3_3") (pintype "bidirectional"))
      (node (ref "U1") (pin "38") (pinfunction "PC7_38") (pintype "bidirectional"))
    )
    (net (code "64") (name "/UART6-TX-GPS") (class "Default")
      (node (ref "J19") (pin "2") (pinfunction "2_2") (pintype "bidirectional"))
      (node (ref "U1") (pin "37") (pinfunction "PC6_37") (pintype "bidirectional"))
    )
    (net (code "65") (name "/USD-CD") (class "Default")
      (node (ref "J23") (pin "CD") (pinfunction "CD-TERM_CD") (pintype "bidirectional"))
      (node (ref "R36") (pin "1") (pinfunction "1_1") (pintype "passive"))
      (node (ref "U1") (pin "33") (pinfunction "PB12_33") (pintype "bidirectional"))
    )
    (net (code "66") (name "3.3V") (class "Default")
      (node (ref "C10") (pin "2") (pinfunction "2_2") (pintype "passive"))
      (node (ref "C13") (pin "2") (pinfunction "2_2") (pintype "passive"))
      (node (ref "C14") (pin "2") (pinfunction "2_2") (pintype "passive"))
      (node (ref "C15") (pin "2") (pinfunction "2_2") (pintype "passive"))
      (node (ref "C16") (pin "2") (pinfunction "2_2") (pintype "passive"))
      (node (ref "C5") (pin "2") (pinfunction "2_2") (pintype "passive"))
      (node (ref "C6") (pin "2") (pinfunction "2_2") (pintype "passive"))
      (node (ref "C7") (pin "2") (pinfunction "2_2") (pintype "passive"))
      (node (ref "C8") (pin "2") (pinfunction "2_2") (pintype "passive"))
      (node (ref "C9") (pin "2") (pinfunction "2_2") (pintype "passive"))
      (node (ref "J23") (pin "4") (pinfunction "VCC_4") (pintype "bidirectional"))
      (node (ref "R1") (pin "1") (pinfunction "1_1") (pintype "passive"))
      (node (ref "R25") (pin "2") (pinfunction "2_2") (pintype "passive"))
      (node (ref "R3") (pin "2") (pinfunction "2_2") (pintype "passive"))
      (node (ref "R31") (pin "2") (pinfunction "2_2") (pintype "passive"))
      (node (ref "R33") (pin "2") (pinfunction "2_2") (pintype "passive"))
      (node (ref "R34") (pin "2") (pinfunction "2_2") (pintype "passive"))
      (node (ref "R36") (pin "2") (pinfunction "2_2") (pintype "passive"))
      (node (ref "U1") (pin "1") (pinfunction "VBAT_1") (pintype "power_in"))
      (node (ref "U1") (pin "13") (pinfunction "VDDA_13") (pintype "power_in"))
      (node (ref "U1") (pin "19") (pinfunction "VDD_19") (pintype "power_in"))
      (node (ref "U1") (pin "32") (pinfunction "VDD_32") (pintype "power_in"))
      (node (ref "U1") (pin "48") (pinfunction "VDD_48") (pintype "power_in"))
      (node (ref "U1") (pin "64") (pinfunction "VDD_64") (pintype "power_in"))
      (node (ref "U2") (pin "1") (pinfunction "VDD_1") (pintype "power_in"))
      (node (ref "U3") (pin "1") (pinfunction "RESV_1") (pintype "bidirectional"))
      (node (ref "U3") (pin "13") (pinfunction "VDD_13") (pintype "bidirectional"))
      (node (ref "U3") (pin "8") (pinfunction "VDDIO_8") (pintype "bidirectional"))
      (node (ref "U4") (pin "5") (pinfunction "OUT_5") (pintype "passive"))
      (node (ref "XBEE") (pin "1") (pinfunction "VDD_1") (pintype "power_in"))
    )
    (net (code "67") (name "5V") (class "Default")
      (node (ref "C3") (pin "2") (pinfunction "2_2") (pintype "passive"))
      (node (ref "J11") (pin "2") (pinfunction "2_2") (pintype "bidirectional"))
      (node (ref "J15") (pin "2") (pinfunction "2_2") (pintype "bidirectional"))
      (node (ref "J19") (pin "1") (pinfunction "1_1") (pintype "bidirectional"))
      (node (ref "J4") (pin "2") (pinfunction "2_2") (pintype "bidirectional"))
      (node (ref "J9") (pin "2") (pinfunction "2_2") (pintype "bidirectional"))
      (node (ref "Q7") (pin "1") (pinfunction "S_1") (pintype "passive"))
      (node (ref "Q7") (pin "2") (pinfunction "S_2") (pintype "passive"))
      (node (ref "Q7") (pin "3") (pinfunction "S_3") (pintype "passive"))
      (node (ref "R11") (pin "1") (pinfunction "1_1") (pintype "passive"))
      (node (ref "R13") (pin "1") (pinfunction "1_1") (pintype "passive"))
      (node (ref "R14") (pin "1") (pinfunction "1_1") (pintype "passive"))
      (node (ref "R16") (pin "1") (pinfunction "1_1") (pintype "passive"))
      (node (ref "R18") (pin "1") (pinfunction "1_1") (pintype "passive"))
      (node (ref "R8") (pin "1") (pinfunction "1_1") (pintype "passive"))
      (node (ref "R9") (pin "1") (pinfunction "1_1") (pintype "passive"))
      (node (ref "U4") (pin "1") (pinfunction "IN_1") (pintype "input"))
      (node (ref "U4") (pin "3") (pinfunction "EN_3") (pintype "input"))
    )
    (net (code "68") (name "5Vin") (class "Default")
      (node (ref "D1") (pin "C") (pinfunction "2_C") (pintype "passive"))
      (node (ref "J22") (pin "1") (pinfunction "VBUS_1") (pintype "bidirectional"))
      (node (ref "J5") (pin "1") (pinfunction "1_1") (pintype "bidirectional"))
      (node (ref "Q7") (pin "10") (pinfunction "D_10") (pintype "passive"))
      (node (ref "Q7") (pin "5") (pinfunction "D_5") (pintype "passive"))
      (node (ref "Q7") (pin "6") (pinfunction "D_6") (pintype "passive"))
      (node (ref "Q7") (pin "7") (pinfunction "D_7") (pintype "passive"))
      (node (ref "Q7") (pin "8") (pinfunction "D_8") (pintype "passive"))
      (node (ref "Q7") (pin "9") (pinfunction "D_9") (pintype "passive"))
    )
    (net (code "69") (name "GND") (class "Default")
      (node (ref "C1") (pin "1") (pinfunction "1_1") (pintype "passive"))
      (node (ref "C10") (pin "1") (pinfunction "1_1") (pintype "passive"))
      (node (ref "C11") (pin "1") (pinfunction "1_1") (pintype "passive"))
      (node (ref "C12") (pin "1") (pinfunction "1_1") (pintype "passive"))
      (node (ref "C13") (pin "1") (pinfunction "1_1") (pintype "passive"))
      (node (ref "C14") (pin "1") (pinfunction "1_1") (pintype "passive"))
      (node (ref "C15") (pin "1") (pinfunction "1_1") (pintype "passive"))
      (node (ref "C16") (pin "1") (pinfunction "1_1") (pintype "passive"))
      (node (ref "C17") (pin "1") (pinfunction "1_1") (pintype "passive"))
      (node (ref "C2") (pin "1") (pinfunction "1_1") (pintype "passive"))
      (node (ref "C3") (pin "1") (pinfunction "1_1") (pintype "passive"))
      (node (ref "C4") (pin "1") (pinfunction "1_1") (pintype "passive"))
      (node (ref "C5") (pin "1") (pinfunction "1_1") (pintype "passive"))
      (node (ref "C6") (pin "1") (pinfunction "1_1") (pintype "passive"))
      (node (ref "C7") (pin "1") (pinfunction "1_1") (pintype "passive"))
      (node (ref "C8") (pin "1") (pinfunction "1_1") (pintype "passive"))
      (node (ref "C9") (pin "1") (pinfunction "1_1") (pintype "passive"))
      (node (ref "D1") (pin "A") (pinfunction "1_A") (pintype "passive"))
      (node (ref "J1") (pin "2") (pinfunction "2_2") (pintype "bidirectional"))
      (node (ref "J10") (pin "2") (pinfunction "2_2") (pintype "bidirectional"))
      (node (ref "J11") (pin "3") (pinfunction "3_3") (pintype "bidirectional"))
      (node (ref "J12") (pin "2") (pinfunction "2_2") (pintype "bidirectional"))
      (node (ref "J13") (pin "2") (pinfunction "2_2") (pintype "bidirectional"))
      (node (ref "J14") (pin "2") (pinfunction "2_2") (pintype "bidirectional"))
      (node (ref "J15") (pin "3") (pinfunction "3_3") (pintype "bidirectional"))
      (node (ref "J16") (pin "3") (pinfunction "3_3") (pintype "bidirectional"))
      (node (ref "J17") (pin "3") (pinfunction "3_3") (pintype "bidirectional"))
      (node (ref "J18") (pin "4") (pinfunction "4_4") (pintype "bidirectional"))
      (node (ref "J19") (pin "4") (pinfunction "4_4") (pintype "bidirectional"))
      (node (ref "J2") (pin "2") (pinfunction "2_2") (pintype "bidirectional"))
      (node (ref "J20") (pin "3") (pinfunction "3_3") (pintype "bidirectional"))
      (node (ref "J21") (pin "4") (pinfunction "4_4") (pintype "bidirectional"))
      (node (ref "J22") (pin "5") (pinfunction "GND_5") (pintype "bidirectional"))
      (node (ref "J22") (pin "S1A") (pinfunction "S1_S1A") (pintype "bidirectional"))
      (node (ref "J22") (pin "S1B") (pinfunction "S1_S1B") (pintype "bidirectional"))
      (node (ref "J22") (pin "S2A") (pinfunction "S2_S2A") (pintype "bidirectional"))
      (node (ref "J22") (pin "S2B") (pinfunction "S2_S2B") (pintype "bidirectional"))
      (node (ref "J22") (pin "S3") (pinfunction "S3_S3") (pintype "bidirectional"))
      (node (ref "J22") (pin "S4") (pinfunction "S4_S4") (pintype "bidirectional"))
      (node (ref "J23") (pin "6") (pinfunction "GND_6") (pintype "bidirectional"))
      (node (ref "J23") (pin "GND") (pinfunction "GND-TERM_GND") (pintype "bidirectional"))
      (node (ref "J23") (pin "S1") (pinfunction "SHIELD_S1") (pintype "bidirectional"))
      (node (ref "J23") (pin "S2") (pinfunction "SHIELD_S2") (pintype "bidirectional"))
      (node (ref "J23") (pin "S3") (pinfunction "SHIELD_S3") (pintype "bidirectional"))
      (node (ref "J23") (pin "S4") (pinfunction "SHIELD_S4") (pintype "bidirectional"))
      (node (ref "J23") (pin "S5") (pinfunction "SHIELD_S5") (pintype "bidirectional"))
      (node (ref "J3") (pin "2") (pinfunction "2_2") (pintype "bidirectional"))
      (node (ref "J4") (pin "3") (pinfunction "3_3") (pintype "bidirectional"))
      (node (ref "J5") (pin "2") (pinfunction "2_2") (pintype "bidirectional"))
      (node (ref "J6") (pin "2") (pinfunction "2_2") (pintype "bidirectional"))
      (node (ref "J7") (pin "2") (pinfunction "2_2") (pintype "bidirectional"))
      (node (ref "J8") (pin "2") (pinfunction "2_2") (pintype "bidirectional"))
      (node (ref "J9") (pin "3") (pinfunction "3_3") (pintype "bidirectional"))
      (node (ref "LED1") (pin "C") (pinfunction "C_C") (pintype "passive"))
      (node (ref "LED10") (pin "C") (pinfunction "C_C") (pintype "passive"))
      (node (ref "LED11") (pin "C") (pinfunction "C_C") (pintype "passive"))
      (node (ref "LED2") (pin "C") (pinfunction "C_C") (pintype "passive"))
      (node (ref "LED3") (pin "C") (pinfunction "C_C") (pintype "passive"))
      (node (ref "LED4") (pin "C") (pinfunction "C_C") (pintype "passive"))
      (node (ref "LED6") (pin "C") (pinfunction "C_C") (pintype "passive"))
      (node (ref "LED7") (pin "C") (pinfunction "C_C") (pintype "passive"))
      (node (ref "LED9") (pin "C") (pinfunction "C_C") (pintype "passive"))
      (node (ref "Q1") (pin "1") (pinfunction "S_1") (pintype "passive"))
      (node (ref "Q1") (pin "4") (pinfunction "S_4") (pintype "passive"))
      (node (ref "Q2") (pin "1") (pinfunction "S_1") (pintype "passive"))
      (node (ref "Q2") (pin "4") (pinfunction "S_4") (pintype "passive"))
      (node (ref "Q3") (pin "1") (pinfunction "S_1") (pintype "passive"))
      (node (ref "Q3") (pin "4") (pinfunction "S_4") (pintype "passive"))
      (node (ref "Q4") (pin "1") (pinfunction "S_1") (pintype "passive"))
      (node (ref "Q4") (pin "4") (pinfunction "S_4") (pintype "passive"))
      (node (ref "Q5") (pin "1") (pinfunction "S_1") (pintype "passive"))
      (node (ref "Q5") (pin "4") (pinfunction "S_4") (pintype "passive"))
      (node (ref "Q6") (pin "1") (pinfunction "S_1") (pintype "passive"))
      (node (ref "Q7") (pin "4") (pinfunction "G_4") (pintype "passive"))
      (node (ref "R27") (pin "2") (pinfunction "2_2") (pintype "passive"))
      (node (ref "R29") (pin "2") (pinfunction "2_2") (pintype "passive"))
      (node (ref "R30") (pin "2") (pinfunction "2_2") (pintype "passive"))
      (node (ref "R32") (pin "2") (pinfunction "2_2") (pintype "passive"))
      (node (ref "S1") (pin "3") (pinfunction "2_3") (pintype "passive"))
      (node (ref "S1") (pin "4") (pinfunction "2_4") (pintype "passive"))
      (node (ref "S2") (pin "P1") (pinfunction "P$1_P1") (pintype "bidirectional"))
      (node (ref "S3") (pin "P1") (pinfunction "P$1_P1") (pintype "bidirectional"))
      (node (ref "S4") (pin "P1") (pinfunction "P$1_P1") (pintype "bidirectional"))
      (node (ref "S5") (pin "P1") (pinfunction "P$1_P1") (pintype "bidirectional"))
      (node (ref "U1") (pin "12") (pinfunction "VSSA_12") (pintype "power_in"))
      (node (ref "U1") (pin "18") (pinfunction "VSS_18") (pintype "power_in"))
      (node (ref "U1") (pin "63") (pinfunction "VSS_63") (pintype "power_in"))
      (node (ref "U2") (pin "2") (pinfunction "PS_2") (pintype "input"))
      (node (ref "U2") (pin "3") (pinfunction "GND_3") (pintype "power_in"))
      (node (ref "U3") (pin "11") (pinfunction "FSYNC_11") (pintype "bidirectional"))
      (node (ref "U3") (pin "18") (pinfunction "GND_18") (pintype "bidirectional"))
      (node (ref "U3") (pin "20") (pinfunction "RESV_20") (pintype "bidirectional"))
      (node (ref "U4") (pin "2") (pinfunction "GND_2") (pintype "input"))
      (node (ref "XBEE") (pin "10") (pinfunction "GND_10") (pintype "power_in"))
    )
    (net (code "70") (name "Net-(J4-Pad1)") (class "Default")
      (node (ref "J4") (pin "1") (pinfunction "1_1") (pintype "bidirectional"))
      (node (ref "R26") (pin "2") (pinfunction "2_2") (pintype "passive"))
    )
    (net (code "71") (name "Net-(J9-Pad1)") (class "Default")
      (node (ref "J9") (pin "1") (pinfunction "1_1") (pintype "bidirectional"))
      (node (ref "R28") (pin "2") (pinfunction "2_2") (pintype "passive"))
    )
    (net (code "72") (name "Net-(LED1-PadA)") (class "Default")
      (node (ref "LED1") (pin "A") (pinfunction "A_A") (pintype "passive"))
      (node (ref "R1") (pin "2") (pinfunction "2_2") (pintype "passive"))
    )
    (net (code "73") (name "Net-(LED2-PadA)") (class "Default")
      (node (ref "LED2") (pin "A") (pinfunction "A_A") (pintype "passive"))
      (node (ref "R2") (pin "2") (pinfunction "2_2") (pintype "passive"))
    )
    (net (code "74") (name "Net-(LED3-PadA)") (class "Default")
      (node (ref "LED3") (pin "A") (pinfunction "A_A") (pintype "passive"))
      (node (ref "R9") (pin "2") (pinfunction "2_2") (pintype "passive"))
    )
    (net (code "75") (name "Net-(LED4-PadA)") (class "Default")
      (node (ref "LED4") (pin "A") (pinfunction "A_A") (pintype "passive"))
      (node (ref "R10") (pin "2") (pinfunction "2_2") (pintype "passive"))
    )
    (net (code "76") (name "Net-(LED5-B+)") (class "Default")
      (node (ref "LED5") (pin "A1") (pinfunction "B+_A1") (pintype "passive"))
      (node (ref "R13") (pin "2") (pinfunction "2_2") (pintype "passive"))
    )
    (net (code "77") (name "Net-(LED5-B-)") (class "Default")
      (node (ref "LED5") (pin "C1") (pinfunction "B-_C1") (pintype "passive"))
      (node (ref "LED8") (pin "C1") (pinfunction "B-_C1") (pintype "passive"))
      (node (ref "Q3") (pin "6") (pinfunction "D_6") (pintype "passive"))
    )
    (net (code "78") (name "Net-(LED5-G+)") (class "Default")
      (node (ref "LED5") (pin "A3") (pinfunction "G+_A3") (pintype "passive"))
      (node (ref "R11") (pin "2") (pinfunction "2_2") (pintype "passive"))
    )
    (net (code "79") (name "Net-(LED5-G-)") (class "Default")
      (node (ref "LED5") (pin "C3") (pinfunction "G-_C3") (pintype "passive"))
      (node (ref "LED8") (pin "C3") (pinfunction "G-_C3") (pintype "passive"))
      (node (ref "Q3") (pin "3") (pinfunction "D_3") (pintype "passive"))
    )
    (net (code "80") (name "Net-(LED5-R+)") (class "Default")
      (node (ref "LED5") (pin "A2") (pinfunction "R+_A2") (pintype "passive"))
      (node (ref "R8") (pin "2") (pinfunction "2_2") (pintype "passive"))
    )
    (net (code "81") (name "Net-(LED5-R-)") (class "Default")
      (node (ref "LED5") (pin "C2") (pinfunction "R-_C2") (pintype "passive"))
      (node (ref "LED8") (pin "C2") (pinfunction "R-_C2") (pintype "passive"))
      (node (ref "Q6") (pin "6") (pinfunction "D_6") (pintype "passive"))
    )
    (net (code "82") (name "Net-(LED6-PadA)") (class "Default")
      (node (ref "LED6") (pin "A") (pinfunction "A_A") (pintype "passive"))
      (node (ref "R12") (pin "2") (pinfunction "2_2") (pintype "passive"))
    )
    (net (code "83") (name "Net-(LED7-PadA)") (class "Default")
      (node (ref "LED7") (pin "A") (pinfunction "A_A") (pintype "passive"))
      (node (ref "R15") (pin "2") (pinfunction "2_2") (pintype "passive"))
    )
    (net (code "84") (name "Net-(LED8-B+)") (class "Default")
      (node (ref "LED8") (pin "A1") (pinfunction "B+_A1") (pintype "passive"))
      (node (ref "R18") (pin "2") (pinfunction "2_2") (pintype "passive"))
    )
    (net (code "85") (name "Net-(LED8-G+)") (class "Default")
      (node (ref "LED8") (pin "A3") (pinfunction "G+_A3") (pintype "passive"))
      (node (ref "R16") (pin "2") (pinfunction "2_2") (pintype "passive"))
    )
    (net (code "86") (name "Net-(LED8-R+)") (class "Default")
      (node (ref "LED8") (pin "A2") (pinfunction "R+_A2") (pintype "passive"))
      (node (ref "R14") (pin "2") (pinfunction "2_2") (pintype "passive"))
    )
    (net (code "87") (name "Net-(LED9-PadA)") (class "Default")
      (node (ref "LED9") (pin "A") (pinfunction "A_A") (pintype "passive"))
      (node (ref "R17") (pin "2") (pinfunction "2_2") (pintype "passive"))
    )
    (net (code "88") (name "Net-(LED10-PadA)") (class "Default")
      (node (ref "LED10") (pin "A") (pinfunction "A_A") (pintype "passive"))
      (node (ref "R23") (pin "2") (pinfunction "2_2") (pintype "passive"))
    )
    (net (code "89") (name "Net-(LED11-PadA)") (class "Default")
      (node (ref "LED11") (pin "A") (pinfunction "A_A") (pintype "passive"))
      (node (ref "R24") (pin "2") (pinfunction "2_2") (pintype "passive"))
    )
    (net (code "90") (name "Net-(U1B-VCAP_1)") (class "Default")
      (node (ref "C12") (pin "2") (pinfunction "2_2") (pintype "passive"))
      (node (ref "U1") (pin "31") (pinfunction "VCAP_1_31") (pintype "passive"))
    )
    (net (code "91") (name "Net-(U1B-VCAP_2)") (class "Default")
      (node (ref "C11") (pin "2") (pinfunction "2_2") (pintype "passive"))
      (node (ref "U1") (pin "47") (pinfunction "VCAP_2_47") (pintype "passive"))
    )
    (net (code "92") (name "Net-(U4-BP)") (class "Default")
      (node (ref "C4") (pin "2") (pinfunction "2_2") (pintype "passive"))
      (node (ref "U4") (pin "4") (pinfunction "BP_4") (pintype "input"))
    )
    (net (code "93") (name "unconnected-(U3-AUX_CL-Pad7)") (class "Default")
      (node (ref "U3") (pin "7") (pinfunction "AUX_CL_7") (pintype "bidirectional"))
    )
    (net (code "94") (name "unconnected-(U3-AUX_DA-Pad21)") (class "Default")
      (node (ref "U3") (pin "21") (pinfunction "AUX_DA_21") (pintype "bidirectional"))
    )
    (net (code "95") (name "unconnected-(U3-INT-Pad12)") (class "Default")
      (node (ref "U3") (pin "12") (pinfunction "INT_12") (pintype "bidirectional"))
    )
    (net (code "96") (name "unconnected-(XBEE-CTS-Pad12)") (class "Default")
      (node (ref "XBEE") (pin "12") (pinfunction "CTS_12") (pintype "output"))
    )
    (net (code "97") (name "unconnected-(XBEE-DIO1-Pad19)") (class "Default")
      (node (ref "XBEE") (pin "19") (pinfunction "DIO1_19") (pintype "bidirectional"))
    )
    (net (code "98") (name "unconnected-(XBEE-DIO2-Pad18)") (class "Default")
      (node (ref "XBEE") (pin "18") (pinfunction "DIO2_18") (pintype "bidirectional"))
    )
    (net (code "99") (name "unconnected-(XBEE-DIO3-Pad17)") (class "Default")
      (node (ref "XBEE") (pin "17") (pinfunction "DIO3_17") (pintype "bidirectional"))
    )
    (net (code "100") (name "unconnected-(XBEE-DIO4-Pad11)") (class "Default")
      (node (ref "XBEE") (pin "11") (pinfunction "DIO4_11") (pintype "bidirectional"))
    )
    (net (code "101") (name "unconnected-(XBEE-DIO5-Pad15)") (class "Default")
      (node (ref "XBEE") (pin "15") (pinfunction "DIO5_15") (pintype "bidirectional"))
    )
    (net (code "102") (name "unconnected-(XBEE-DIO9-Pad13)") (class "Default")
      (node (ref "XBEE") (pin "13") (pinfunction "DIO9_13") (pintype "bidirectional"))
    )
    (net (code "103") (name "unconnected-(XBEE-DIO11-Pad7)") (class "Default")
      (node (ref "XBEE") (pin "7") (pinfunction "DIO11_7") (pintype "bidirectional"))
    )
    (net (code "104") (name "unconnected-(XBEE-DIO12-Pad4)") (class "Default")
      (node (ref "XBEE") (pin "4") (pinfunction "DIO12_4") (pintype "bidirectional"))
    )
    (net (code "105") (name "unconnected-(XBEE-DTR-Pad9)") (class "Default")
      (node (ref "XBEE") (pin "9") (pinfunction "DTR_9") (pintype "bidirectional"))
    )
    (net (code "106") (name "unconnected-(XBEE-RES-Pad8)") (class "Default")
      (node (ref "XBEE") (pin "8") (pinfunction "RES_8") (pintype "bidirectional"))
    )
    (net (code "107") (name "unconnected-(XBEE-RES-Pad14)") (class "Default")
      (node (ref "XBEE") (pin "14") (pinfunction "RES_14") (pintype "bidirectional"))
    )
    (net (code "108") (name "unconnected-(XBEE-RESET-Pad5)") (class "Default")
      (node (ref "XBEE") (pin "5") (pinfunction "RESET_5") (pintype "input"))
    )
    (net (code "109") (name "unconnected-(XBEE-RTS-Pad16)") (class "Default")
      (node (ref "XBEE") (pin "16") (pinfunction "RTS_16") (pintype "input"))
    )
  )
)
